# PCB_Reflow_Plate.net
KiCad netlist of a schematic drawn in Altium Designer
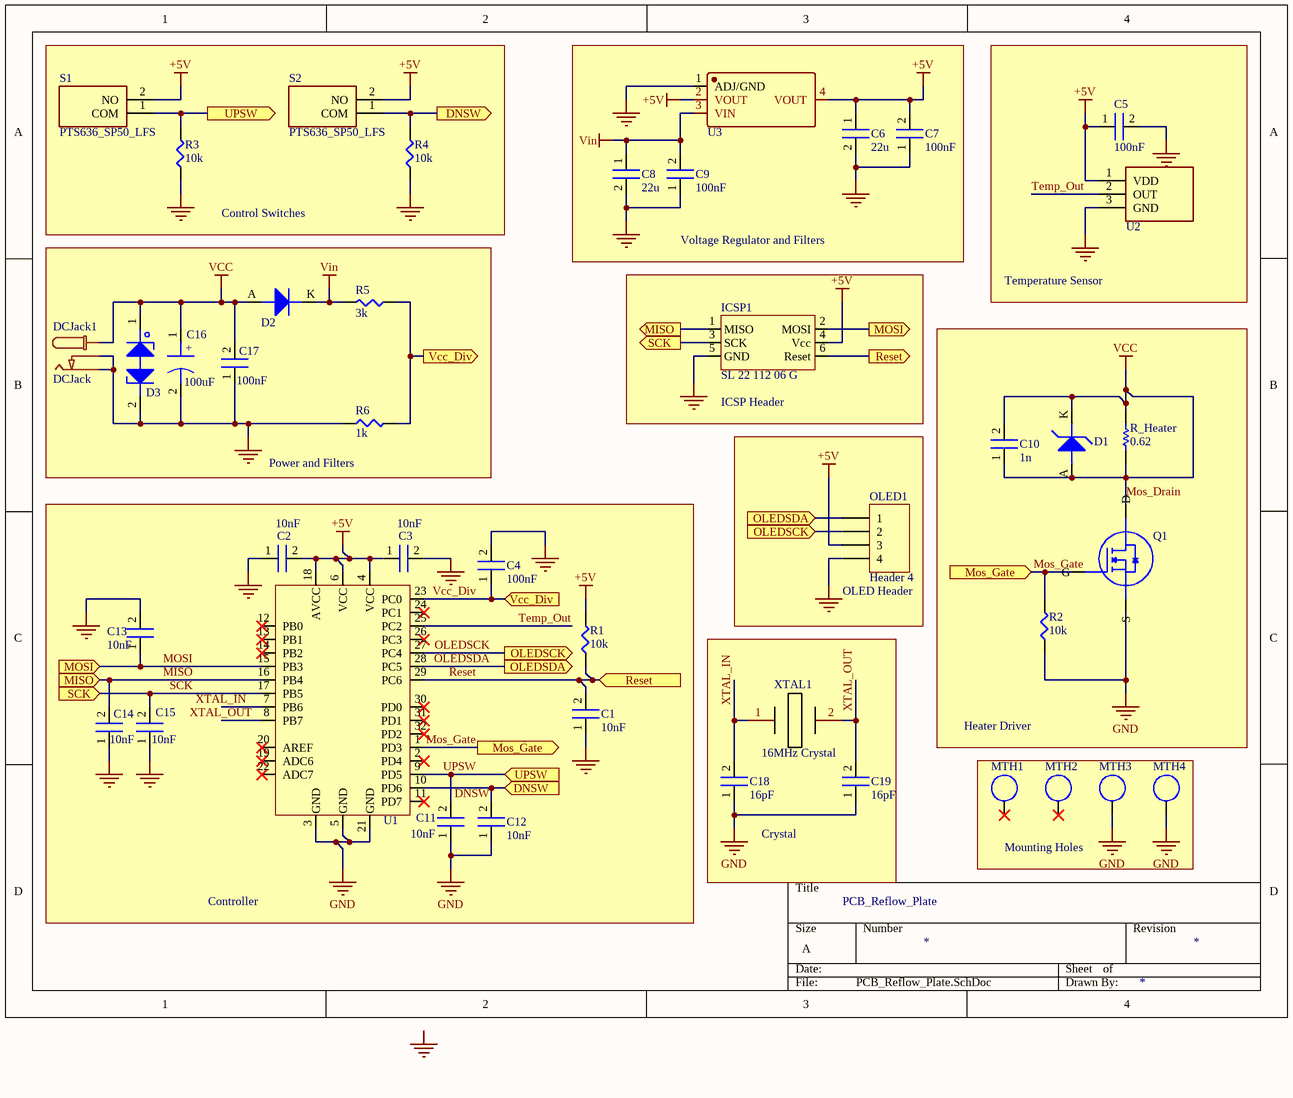
[diagram p0: PCB_Reflow_Plate.SchDoc]

(export (version "E")
  (design (tool "Eeschema 10.0.6"))
  (components
    (comp (ref "C1")
      (value "10n 0402")
      (footprint "0402B103J500CT")
      (description "Cap Ceramic 0.01uF 100V X7S 20% SMD 0402 125C Paper T/R")
      (fields
        (field (name "MANUFACTURER") "TDK")
        (field (name "MANUFACTURER PART NUMBER") "C1005X7S2A103M050BB")
        (field (name "CAPACITANCE") "10nF")
      )
      (libsource (lib "PCB_Reflow_Plate_SchLib") (part "C1005X7S2A103M050BB"))
    )
    (comp (ref "C2")
      (value "10n 0402")
      (footprint "0402B103J500CT")
      (description "Cap Ceramic 0.01uF 100V X7S 20% SMD 0402 125C Paper T/R")
      (fields
        (field (name "MANUFACTURER") "TDK")
        (field (name "MANUFACTURER PART NUMBER") "C1005X7S2A103M050BB")
        (field (name "CAPACITANCE") "10nF")
      )
      (libsource (lib "PCB_Reflow_Plate_SchLib") (part "C1005X7S2A103M050BB"))
    )
    (comp (ref "C3")
      (value "10n 0402")
      (footprint "0402B103J500CT")
      (description "Cap Ceramic 0.01uF 100V X7S 20% SMD 0402 125C Paper T/R")
      (fields
        (field (name "MANUFACTURER") "TDK")
        (field (name "MANUFACTURER PART NUMBER") "C1005X7S2A103M050BB")
        (field (name "CAPACITANCE") "10nF")
      )
      (libsource (lib "PCB_Reflow_Plate_SchLib") (part "C1005X7S2A103M050BB"))
    )
    (comp (ref "C4")
      (value "100n 0603")
      (footprint "0603B104K250CT")
      (description "CAP CER 0.1UF 100V X7R 0603")
      (fields
        (field (name "MANUFACTURER") "Murata")
        (field (name "MANUFACTURER PART NUMBER") "GRM188R72A104KA35D")
        (field (name "CAPACITANCE") "100nF")
      )
      (libsource (lib "PCB_Reflow_Plate_SchLib") (part "GRM188R72A104KA35D"))
    )
    (comp (ref "C5")
      (value "100n 0603")
      (footprint "0603B104K250CT")
      (description "CAP CER 0.1UF 100V X7R 0603")
      (fields
        (field (name "MANUFACTURER") "Murata")
        (field (name "MANUFACTURER PART NUMBER") "GRM188R72A104KA35D")
        (field (name "CAPACITANCE") "100nF")
      )
      (libsource (lib "PCB_Reflow_Plate_SchLib") (part "GRM188R72A104KA35D"))
    )
    (comp (ref "C6")
      (value "22u 0805")
      (footprint "CL21A226MAYNNNE")
      (description "25V 22uF X5R ±20% 0805 Multilayer Ceramic Capacitors MLCC - SMD/SMT ROHS")
      (fields
        (field (name "MANUFACTURER") "Samsung")
        (field (name "MANUFACTURER PART NUMBER") "CL21A226MAYNNNE")
        (field (name "CAPACITANCE") "22u")
      )
      (libsource (lib "PCB_Reflow_Plate_SchLib") (part "CL21A226MAYNNNE"))
    )
    (comp (ref "C7")
      (value "100n 0603")
      (footprint "0603B104K250CT")
      (description "CAP CER 0.1UF 100V X7R 0603")
      (fields
        (field (name "MANUFACTURER") "Murata")
        (field (name "MANUFACTURER PART NUMBER") "GRM188R72A104KA35D")
        (field (name "CAPACITANCE") "100nF")
      )
      (libsource (lib "PCB_Reflow_Plate_SchLib") (part "GRM188R72A104KA35D"))
    )
    (comp (ref "C8")
      (value "22u 0805")
      (footprint "CL21A226MAYNNNE")
      (description "25V 22uF X5R ±20% 0805 Multilayer Ceramic Capacitors MLCC - SMD/SMT ROHS")
      (fields
        (field (name "MANUFACTURER") "Samsung")
        (field (name "MANUFACTURER PART NUMBER") "CL21A226MAYNNNE")
        (field (name "CAPACITANCE") "22u")
      )
      (libsource (lib "PCB_Reflow_Plate_SchLib") (part "CL21A226MAYNNNE"))
    )
    (comp (ref "C9")
      (value "100n 0603")
      (footprint "0603B104K250CT")
      (description "CAP CER 0.1UF 100V X7R 0603")
      (fields
        (field (name "MANUFACTURER") "Murata")
        (field (name "MANUFACTURER PART NUMBER") "GRM188R72A104KA35D")
        (field (name "CAPACITANCE") "100nF")
      )
      (libsource (lib "PCB_Reflow_Plate_SchLib") (part "GRM188R72A104KA35D"))
    )
    (comp (ref "C10")
      (value "1n 0805")
      (footprint "FM21X102K501PXG")
      (description "0805 1 nF 250 V ±10% Tolerance X7R SMT Multilayer Ceramic Capacitor")
      (fields
        (field (name "MANUFACTURER") "Murata")
        (field (name "MANUFACTURER PART NUMBER") "GRM21AR72E102KW01D")
        (field (name "CAPACITANCE") "1n")
      )
      (libsource (lib "PCB_Reflow_Plate_SchLib") (part "GRM21AR72E102KW01D"))
    )
    (comp (ref "C11")
      (value "10n 0402")
      (footprint "0402B103J500CT")
      (description "Cap Ceramic 0.01uF 100V X7S 20% SMD 0402 125C Paper T/R")
      (fields
        (field (name "MANUFACTURER") "TDK")
        (field (name "MANUFACTURER PART NUMBER") "C1005X7S2A103M050BB")
        (field (name "CAPACITANCE") "10nF")
      )
      (libsource (lib "PCB_Reflow_Plate_SchLib") (part "C1005X7S2A103M050BB"))
    )
    (comp (ref "C12")
      (value "10n 0402")
      (footprint "0402B103J500CT")
      (description "Cap Ceramic 0.01uF 100V X7S 20% SMD 0402 125C Paper T/R")
      (fields
        (field (name "MANUFACTURER") "TDK")
        (field (name "MANUFACTURER PART NUMBER") "C1005X7S2A103M050BB")
        (field (name "CAPACITANCE") "10nF")
      )
      (libsource (lib "PCB_Reflow_Plate_SchLib") (part "C1005X7S2A103M050BB"))
    )
    (comp (ref "C13")
      (value "10n 0402")
      (footprint "0402B103J500CT")
      (description "Cap Ceramic 0.01uF 100V X7S 20% SMD 0402 125C Paper T/R")
      (fields
        (field (name "MANUFACTURER") "TDK")
        (field (name "MANUFACTURER PART NUMBER") "C1005X7S2A103M050BB")
        (field (name "CAPACITANCE") "10nF")
      )
      (libsource (lib "PCB_Reflow_Plate_SchLib") (part "C1005X7S2A103M050BB"))
    )
    (comp (ref "C14")
      (value "10n 0402")
      (footprint "0402B103J500CT")
      (description "Cap Ceramic 0.01uF 100V X7S 20% SMD 0402 125C Paper T/R")
      (fields
        (field (name "MANUFACTURER") "TDK")
        (field (name "MANUFACTURER PART NUMBER") "C1005X7S2A103M050BB")
        (field (name "CAPACITANCE") "10nF")
      )
      (libsource (lib "PCB_Reflow_Plate_SchLib") (part "C1005X7S2A103M050BB"))
    )
    (comp (ref "C15")
      (value "10n 0402")
      (footprint "0402B103J500CT")
      (description "Cap Ceramic 0.01uF 100V X7S 20% SMD 0402 125C Paper T/R")
      (fields
        (field (name "MANUFACTURER") "TDK")
        (field (name "MANUFACTURER PART NUMBER") "C1005X7S2A103M050BB")
        (field (name "CAPACITANCE") "10nF")
      )
      (libsource (lib "PCB_Reflow_Plate_SchLib") (part "C1005X7S2A103M050BB"))
    )
    (comp (ref "C16")
      (value "100u SMD Polarized")
      (footprint "UWT1V101MCL1GS")
      (fields
        (field (name "MANUFACTURER") "Nichicon")
        (field (name "MANUFACTURER PART NUMBER") "UWT1V101MCL1GS")
        (field (name "TOLERANCE") "20%")
        (field (name "CAPACITANCE") "100uF")
      )
      (libsource (lib "PCB_Reflow_Plate_SchLib") (part "UWT1V101MCL1GS"))
    )
    (comp (ref "C17")
      (value "100n 0603")
      (footprint "0603B104K250CT")
      (description "CAP CER 0.1UF 100V X7R 0603")
      (fields
        (field (name "MANUFACTURER") "Murata")
        (field (name "MANUFACTURER PART NUMBER") "GRM188R72A104KA35D")
        (field (name "CAPACITANCE") "100nF")
      )
      (libsource (lib "PCB_Reflow_Plate_SchLib") (part "GRM188R72A104KA35D"))
    )
    (comp (ref "C18")
      (value "16pf 0603 Capacitor")
      (footprint "NMC0603NPO160J50TRPF")
      (description "Cap Ceramic 16pF 50V C0G 5% SMD 0603 125°C Paper T/R")
      (fields
        (field (name "MANUFACTURER") "NIC Components")
        (field (name "MANUFACTURER PART NUMBER") "NMC0603NPO160J50TRPF")
        (field (name "CAPACITANCE") "16pF")
      )
      (libsource (lib "PCB_Reflow_Plate_SchLib") (part "NMC0603NPO160J50TRPF"))
    )
    (comp (ref "C19")
      (value "16pf 0603 Capacitor")
      (footprint "NMC0603NPO160J50TRPF")
      (description "Cap Ceramic 16pF 50V C0G 5% SMD 0603 125°C Paper T/R")
      (fields
        (field (name "MANUFACTURER") "NIC Components")
        (field (name "MANUFACTURER PART NUMBER") "NMC0603NPO160J50TRPF")
        (field (name "CAPACITANCE") "16pF")
      )
      (libsource (lib "PCB_Reflow_Plate_SchLib") (part "NMC0603NPO160J50TRPF"))
    )
    (comp (ref "D1")
      (value "Zener Diode")
      (footprint "MMSZ24T1G")
      (description "Zener Single Diode, 24 V, 500 mW, SOD-123, 5 %, 2, 150 C RoHS Compliant: Yes")
      (fields
        (field (name "MANUFACTURER") "ON Semiconductor")
        (field (name "MANUFACTURER PART NUMBER") "MMSZ24T1G")
      )
      (libsource (lib "PCB_Reflow_Plate_SchLib") (part "MMSZ24T1G"))
    )
    (comp (ref "D2")
      (value "Diode")
      (footprint "1N4448X-TP")
      (description "1N4448X Series 4 A 75 V 150 mW Surface Mount Switching Diode - SOD-523")
      (fields (field (name "MANUFACTURER") "MCC") (field (name "MANUFACTURER PART NUMBER") "1N4448X-TP"))
      (libsource (lib "PCB_Reflow_Plate_SchLib") (part "1N4448X-TP"))
    )
    (comp (ref "D3")
      (value "TVS bi-directional")
      (footprint "PESD18VF1BLYL")
      (description "TVS DIODE 18VWM 17VC SOD882")
      (fields
        (field (name "MANUFACTURER") "Nexperia")
        (field (name "MANUFACTURER PART NUMBER") "PESD18VF1BLYL")
      )
      (libsource (lib "PCB_Reflow_Plate_SchLib") (part "PESD18VF1BLYL"))
    )
    (comp (ref "DCJack1")
      (value "DCJack")
      (footprint "KLDX-0202-B")
      (description "Conn Power PIN 2 POS Solder RA Thru-Hole 3 Terminal 1 Port")
      (fields (field (name "MANUFACTURER") "Kycon") (field (name "MANUFACTURER PART NUMBER") "KLDX-0202-B"))
      (libsource (lib "PCB_Reflow_Plate_SchLib") (part "KLDX-0202-B"))
    )
    (comp (ref "ICSP1")
      (value "SL 22 112 06 G")
      (footprint "SL 22 112 06 G")
      (description "Conn Unshrouded Header M 6 POS 2.54mm Solder ST Thru-Hole")
      (fields (field (name "MANUFACTURER") "Fischer Elektronik"))
      (libsource (lib "PCB_Reflow_Plate_SchLib") (part "SL 22 112 06 G"))
    )
    (comp (ref "MTH1")
      (value "Mounting Hole 6mm outer 3mm inner")
      (footprint "MTH_6mmOD_3mmID")
      (description "Mounting Hole 6mm outer 3mm inner drill")
      (libsource (lib "PCB_Reflow_Plate_SchLib") (part "MTH_6mmOD_3mmID"))
    )
    (comp (ref "MTH2")
      (value "Mounting Hole 6mm outer 3mm inner")
      (footprint "MTH_6mmOD_3mmID")
      (description "Mounting Hole 6mm outer 3mm inner drill")
      (libsource (lib "PCB_Reflow_Plate_SchLib") (part "MTH_6mmOD_3mmID"))
    )
    (comp (ref "MTH3")
      (value "Mounting Hole 6mm outer 3mm inner")
      (footprint "MTH_6mmOD_3mmID")
      (description "Mounting Hole 6mm outer 3mm inner drill")
      (libsource (lib "PCB_Reflow_Plate_SchLib") (part "MTH_6mmOD_3mmID"))
    )
    (comp (ref "MTH4")
      (value "Mounting Hole 6mm outer 3mm inner")
      (footprint "MTH_6mmOD_3mmID")
      (description "Mounting Hole 6mm outer 3mm inner drill")
      (libsource (lib "PCB_Reflow_Plate_SchLib") (part "MTH_6mmOD_3mmID"))
    )
    (comp (ref "OLED1")
      (value "Header 4")
      (footprint "HDR1X4")
      (description "Header, 4-Pin")
      (fields (field (name "PUBLISHER") "Altium Limited"))
      (libsource (lib "Miscellaneous Connectors") (part "Header 4"))
    )
    (comp (ref "Q1")
      (value "Mosfet DPAK")
      (footprint "AOD442")
      (description "Trans MOSFET N-CH 60V 37A 3-Pin(2+Tab) DPAK")
      (fields
        (field (name "MANUFACTURER") "Alpha & Omega Semiconductor")
        (field (name "MANUFACTURER PART NUMBER") "AOD442")
      )
      (libsource (lib "PCB_Reflow_Plate_SchLib") (part "AOD442"))
    )
    (comp (ref "R1")
      (value "10k 0603")
      (footprint "RTT03103JTP")
      (description "Res Thin Film 0603 10K Ohm 0.5% 0.1W(1/10W) ±50ppm/°C Pad SMD T/R")
      (fields
        (field (name "MANUFACTURER") "Yageo")
        (field (name "MANUFACTURER PART NUMBER") "RT0603DRE0710KL")
        (field (name "RESISTANCE") "10k")
      )
      (libsource (lib "PCB_Reflow_Plate_SchLib") (part "RT0603DRE0710KL"))
    )
    (comp (ref "R2")
      (value "10k 0603")
      (footprint "RTT03103JTP")
      (description "Res Thin Film 0603 10K Ohm 0.5% 0.1W(1/10W) ±50ppm/°C Pad SMD T/R")
      (fields
        (field (name "MANUFACTURER") "Yageo")
        (field (name "MANUFACTURER PART NUMBER") "RT0603DRE0710KL")
        (field (name "RESISTANCE") "10k")
      )
      (libsource (lib "PCB_Reflow_Plate_SchLib") (part "RT0603DRE0710KL"))
    )
    (comp (ref "R3")
      (value "10k 0603")
      (footprint "RTT03103JTP")
      (description "Res Thin Film 0603 10K Ohm 0.5% 0.1W(1/10W) ±50ppm/°C Pad SMD T/R")
      (fields
        (field (name "MANUFACTURER") "Yageo")
        (field (name "MANUFACTURER PART NUMBER") "RT0603DRE0710KL")
        (field (name "RESISTANCE") "10k")
      )
      (libsource (lib "PCB_Reflow_Plate_SchLib") (part "RT0603DRE0710KL"))
    )
    (comp (ref "R4")
      (value "10k 0603")
      (footprint "RTT03103JTP")
      (description "Res Thin Film 0603 10K Ohm 0.5% 0.1W(1/10W) ±50ppm/°C Pad SMD T/R")
      (fields
        (field (name "MANUFACTURER") "Yageo")
        (field (name "MANUFACTURER PART NUMBER") "RT0603DRE0710KL")
        (field (name "RESISTANCE") "10k")
      )
      (libsource (lib "PCB_Reflow_Plate_SchLib") (part "RT0603DRE0710KL"))
    )
    (comp (ref "R5")
      (value "3k 0805")
      (footprint "RTT05302JTP")
      (description "Res Thick Film 0805 3K Ohm 1% 0.125W(1/8W) ±100ppm/C Pad SMD T/R")
      (fields
        (field (name "MANUFACTURER") "Yageo")
        (field (name "MANUFACTURER PART NUMBER") "RC0805FR-073KL")
        (field (name "RESISTANCE") "3k")
      )
      (libsource (lib "PCB_Reflow_Plate_SchLib") (part "RC0805FR-073KL"))
    )
    (comp (ref "R6")
      (value "1k 0805")
      (footprint "CR0805-FX-1001ELF")
      (description "125mW ±100ppm/℃ ±1% 1kΩ 0805 Chip Resistor - Surface Mount ROHS")
      (fields
        (field (name "MANUFACTURER") "Bourns")
        (field (name "MANUFACTURER PART NUMBER") "CR0805-FX-1001ELF")
        (field (name "RESISTANCE") "1k")
      )
      (libsource (lib "PCB_Reflow_Plate_SchLib") (part "CR0805-FX-1001ELF"))
    )
    (comp (ref "R_Heater")
      (value "0.62")
      (description "Resistor")
      (libsource (lib "Simulation Generic Components") (part "Resistor"))
    )
    (comp (ref "S1")
      (value "PTS636_SP50_LFS")
      (footprint "PTS636_SP50_LFS")
      (description "Switch")
      (fields
        (field (name "MANUFACTURER") "C & K COMPONENTS")
        (field (name "MANUFACTURER PART NUMBER") "PTS636 SP50 LFS")
      )
      (libsource (lib "PCB_Reflow_Plate_SchLib") (part "PTS636_SP50_LFS"))
    )
    (comp (ref "S2")
      (value "PTS636_SP50_LFS")
      (footprint "PTS636_SP50_LFS")
      (description "Switch")
      (fields
        (field (name "MANUFACTURER") "C & K COMPONENTS")
        (field (name "MANUFACTURER PART NUMBER") "PTS636 SP50 LFS")
      )
      (libsource (lib "PCB_Reflow_Plate_SchLib") (part "PTS636_SP50_LFS"))
    )
    (comp (ref "U1")
      (value "ATMEGA328P-AU")
      (footprint "atmega328p-au")
      (fields (field (name "MANUFACTURER") "Microchip"))
      (libsource (lib "PCB_Reflow_Plate_SchLib") (part "ATMEGA328P-AU"))
    )
    (comp (ref "U2")
      (value "LMT85LP")
      (footprint "LMT85LP")
      (description "1.8V-Capable, 10 uA Analog Output Temperature Sensor in SC70 and TO-92 3-TO-92 -50 to 150")
      (fields (field (name "MANUFACTURER") "Texas Instruments"))
      (libsource (lib "PCB_Reflow_Plate_SchLib") (part "LMT85LP"))
    )
    (comp (ref "U3")
      (value "AMS1117-5.0")
      (footprint "AMS1117-5.0")
      (fields (field (name "MANUFACTURER") "WPMtek"))
      (libsource (lib "PCB_Reflow_Plate_SchLib") (part "AMS1117-5.0"))
    )
    (comp (ref "XTAL1")
      (value "16MHz Crystal")
      (footprint "ABM7-16.000MHZ-D2Y-T")
      (description "Crystal 16MHz ±20ppm (Tol) ±30ppm (Stability) 18pF FUND 50Ohm 2-Pin Mini-CSMD T/R")
      (fields
        (field (name "MANUFACTURER") "Abracon")
        (field (name "MANUFACTURER PART NUMBER") "ABM7-16.000MHZ-D2Y-T")
      )
      (libsource (lib "PCB_Reflow_Plate_SchLib") (part "ABM7-16.000MHZ-D2Y-T"))
    )
  )
  (nets
    (net (code "1") (name "+5V") (class "Default")
      (node (ref "C2") (pin "2") (pinfunction "2_2") (pintype "passive"))
      (node (ref "C3") (pin "1") (pinfunction "1_1") (pintype "passive"))
      (node (ref "C5") (pin "1") (pinfunction "1_1") (pintype "passive"))
      (node (ref "C6") (pin "1") (pinfunction "1_1") (pintype "passive"))
      (node (ref "C7") (pin "2") (pinfunction "2_2") (pintype "passive"))
      (node (ref "ICSP1") (pin "4") (pinfunction "Vcc_4") (pintype "passive"))
      (node (ref "OLED1") (pin "3") (pinfunction "3_3") (pintype "passive"))
      (node (ref "R1") (pin "2") (pinfunction "2_2") (pintype "passive"))
      (node (ref "S1") (pin "2") (pinfunction "NO_2") (pintype "passive"))
      (node (ref "S2") (pin "2") (pinfunction "NO_2") (pintype "passive"))
      (node (ref "U1") (pin "18") (pinfunction "AVCC_18") (pintype "passive"))
      (node (ref "U1") (pin "4") (pinfunction "VCC_4") (pintype "passive"))
      (node (ref "U1") (pin "6") (pinfunction "VCC_6") (pintype "passive"))
      (node (ref "U2") (pin "1") (pinfunction "VDD_1") (pintype "passive"))
      (node (ref "U3") (pin "2") (pinfunction "VOUT_2") (pintype "passive"))
      (node (ref "U3") (pin "4") (pinfunction "VOUT_4") (pintype "passive"))
    )
    (net (code "2") (name "/DNSW") (class "Default")
      (node (ref "C12") (pin "2") (pinfunction "2_2") (pintype "passive"))
      (node (ref "R4") (pin "2") (pinfunction "2_2") (pintype "passive"))
      (node (ref "S2") (pin "1") (pinfunction "COM_1") (pintype "passive"))
      (node (ref "U1") (pin "10") (pinfunction "PD6_10") (pintype "passive"))
    )
    (net (code "3") (name "/MISO") (class "Default")
      (node (ref "C14") (pin "2") (pinfunction "2_2") (pintype "passive"))
      (node (ref "ICSP1") (pin "1") (pinfunction "MISO_1") (pintype "passive"))
      (node (ref "U1") (pin "16") (pinfunction "PB4_16") (pintype "passive"))
    )
    (net (code "4") (name "/MOSI") (class "Default")
      (node (ref "C13") (pin "1") (pinfunction "1_1") (pintype "passive"))
      (node (ref "ICSP1") (pin "2") (pinfunction "MOSI_2") (pintype "passive"))
      (node (ref "U1") (pin "15") (pinfunction "PB3_15") (pintype "passive"))
    )
    (net (code "5") (name "/Mos_Gate") (class "Default")
      (node (ref "Q1") (pin "3") (pinfunction "G_3") (pintype "passive"))
      (node (ref "R2") (pin "2") (pinfunction "2_2") (pintype "passive"))
      (node (ref "U1") (pin "1") (pinfunction "PD3_1") (pintype "passive"))
    )
    (net (code "6") (name "/OLEDSCK") (class "Default")
      (node (ref "OLED1") (pin "2") (pinfunction "2_2") (pintype "passive"))
      (node (ref "U1") (pin "27") (pinfunction "PC4_27") (pintype "passive"))
    )
    (net (code "7") (name "/OLEDSDA") (class "Default")
      (node (ref "OLED1") (pin "1") (pinfunction "1_1") (pintype "passive"))
      (node (ref "U1") (pin "28") (pinfunction "PC5_28") (pintype "passive"))
    )
    (net (code "8") (name "/Reset") (class "Default")
      (node (ref "C1") (pin "2") (pinfunction "2_2") (pintype "passive"))
      (node (ref "ICSP1") (pin "6") (pinfunction "Reset_6") (pintype "passive"))
      (node (ref "R1") (pin "1") (pinfunction "1_1") (pintype "passive"))
      (node (ref "U1") (pin "29") (pinfunction "PC6_29") (pintype "passive"))
    )
    (net (code "9") (name "/SCK") (class "Default")
      (node (ref "C15") (pin "2") (pinfunction "2_2") (pintype "passive"))
      (node (ref "ICSP1") (pin "3") (pinfunction "SCK_3") (pintype "passive"))
      (node (ref "U1") (pin "17") (pinfunction "PB5_17") (pintype "passive"))
    )
    (net (code "10") (name "/Temp_Out") (class "Default")
      (node (ref "U1") (pin "25") (pinfunction "PC2_25") (pintype "passive"))
      (node (ref "U2") (pin "2") (pinfunction "OUT_2") (pintype "passive"))
    )
    (net (code "11") (name "/UPSW") (class "Default")
      (node (ref "C11") (pin "2") (pinfunction "2_2") (pintype "passive"))
      (node (ref "R3") (pin "2") (pinfunction "2_2") (pintype "passive"))
      (node (ref "S1") (pin "1") (pinfunction "COM_1") (pintype "passive"))
      (node (ref "U1") (pin "9") (pinfunction "PD5_9") (pintype "passive"))
    )
    (net (code "12") (name "/Vcc_Div") (class "Default")
      (node (ref "C4") (pin "1") (pinfunction "1_1") (pintype "passive"))
      (node (ref "R5") (pin "1") (pinfunction "1_1") (pintype "passive"))
      (node (ref "R6") (pin "2") (pinfunction "2_2") (pintype "passive"))
      (node (ref "U1") (pin "23") (pinfunction "PC0_23") (pintype "passive"))
    )
    (net (code "13") (name "/XTAL_IN") (class "Default")
      (node (ref "C18") (pin "2") (pinfunction "2_2") (pintype "passive"))
      (node (ref "U1") (pin "7") (pinfunction "PB6_7") (pintype "passive"))
      (node (ref "XTAL1") (pin "1") (pinfunction "1_1") (pintype "passive"))
    )
    (net (code "14") (name "/XTAL_OUT") (class "Default")
      (node (ref "C19") (pin "2") (pinfunction "2_2") (pintype "passive"))
      (node (ref "U1") (pin "8") (pinfunction "PB7_8") (pintype "passive"))
      (node (ref "XTAL1") (pin "2") (pinfunction "2_2") (pintype "passive"))
    )
    (net (code "15") (name "GND") (class "Default")
      (node (ref "C1") (pin "1") (pinfunction "1_1") (pintype "passive"))
      (node (ref "C11") (pin "1") (pinfunction "1_1") (pintype "passive"))
      (node (ref "C12") (pin "1") (pinfunction "1_1") (pintype "passive"))
      (node (ref "C13") (pin "2") (pinfunction "2_2") (pintype "passive"))
      (node (ref "C14") (pin "1") (pinfunction "1_1") (pintype "passive"))
      (node (ref "C15") (pin "1") (pinfunction "1_1") (pintype "passive"))
      (node (ref "C16") (pin "2") (pinfunction "2_2") (pintype "passive"))
      (node (ref "C17") (pin "1") (pinfunction "1_1") (pintype "passive"))
      (node (ref "C18") (pin "1") (pinfunction "1_1") (pintype "passive"))
      (node (ref "C19") (pin "1") (pinfunction "1_1") (pintype "passive"))
      (node (ref "C2") (pin "1") (pinfunction "1_1") (pintype "passive"))
      (node (ref "C3") (pin "2") (pinfunction "2_2") (pintype "passive"))
      (node (ref "C4") (pin "2") (pinfunction "2_2") (pintype "passive"))
      (node (ref "C5") (pin "2") (pinfunction "2_2") (pintype "passive"))
      (node (ref "C6") (pin "2") (pinfunction "2_2") (pintype "passive"))
      (node (ref "C7") (pin "1") (pinfunction "1_1") (pintype "passive"))
      (node (ref "C8") (pin "2") (pinfunction "2_2") (pintype "passive"))
      (node (ref "C9") (pin "1") (pinfunction "1_1") (pintype "passive"))
      (node (ref "D3") (pin "2") (pinfunction "2_2") (pintype "passive"))
      (node (ref "DCJack1") (pin "P2") (pinfunction "P2_P2") (pintype "passive"))
      (node (ref "DCJack1") (pin "P3") (pinfunction "P3_P3") (pintype "passive"))
      (node (ref "ICSP1") (pin "5") (pinfunction "GND_5") (pintype "passive"))
      (node (ref "MTH3") (pin "1") (pinfunction "1_1") (pintype "passive"))
      (node (ref "MTH4") (pin "1") (pinfunction "1_1") (pintype "passive"))
      (node (ref "OLED1") (pin "4") (pinfunction "4_4") (pintype "passive"))
      (node (ref "Q1") (pin "2") (pinfunction "S_2") (pintype "passive"))
      (node (ref "R2") (pin "1") (pinfunction "1_1") (pintype "passive"))
      (node (ref "R3") (pin "1") (pinfunction "1_1") (pintype "passive"))
      (node (ref "R4") (pin "1") (pinfunction "1_1") (pintype "passive"))
      (node (ref "R6") (pin "1") (pinfunction "1_1") (pintype "passive"))
      (node (ref "U1") (pin "21") (pinfunction "GND_21") (pintype "passive"))
      (node (ref "U1") (pin "3") (pinfunction "GND_3") (pintype "passive"))
      (node (ref "U1") (pin "5") (pinfunction "GND_5") (pintype "passive"))
      (node (ref "U2") (pin "3") (pinfunction "GND_3") (pintype "passive"))
      (node (ref "U3") (pin "1") (pinfunction "ADJ/GND_1") (pintype "passive"))
    )
    (net (code "16") (name "VCC") (class "Default")
      (node (ref "C10") (pin "1") (pinfunction "1_1") (pintype "passive"))
      (node (ref "C10") (pin "2") (pinfunction "2_2") (pintype "passive"))
      (node (ref "C16") (pin "1") (pinfunction "1_1") (pintype "passive"))
      (node (ref "C17") (pin "2") (pinfunction "2_2") (pintype "passive"))
      (node (ref "D1") (pin "A") (pinfunction "A_A") (pintype "passive"))
      (node (ref "D1") (pin "K") (pinfunction "K_K") (pintype "passive"))
      (node (ref "D2") (pin "A") (pinfunction "1_A") (pintype "passive"))
      (node (ref "D3") (pin "1") (pinfunction "1_1") (pintype "passive"))
      (node (ref "DCJack1") (pin "P1") (pinfunction "P1_P1") (pintype "passive"))
      (node (ref "Q1") (pin "1") (pinfunction "D_1") (pintype "passive"))
      (node (ref "R_Heater") (pin "1") (pinfunction "1_1") (pintype "passive"))
      (node (ref "R_Heater") (pin "2") (pinfunction "2_2") (pintype "passive"))
    )
    (net (code "17") (name "Vin") (class "Default")
      (node (ref "C8") (pin "1") (pinfunction "1_1") (pintype "passive"))
      (node (ref "C9") (pin "2") (pinfunction "2_2") (pintype "passive"))
      (node (ref "D2") (pin "K") (pinfunction "2_K") (pintype "passive"))
      (node (ref "R5") (pin "2") (pinfunction "2_2") (pintype "passive"))
      (node (ref "U3") (pin "3") (pinfunction "VIN_3") (pintype "passive"))
    )
    (net (code "18") (name "unconnected-(MTH1-Pad1)") (class "Default")
      (node (ref "MTH1") (pin "1") (pinfunction "1_1") (pintype "passive+no_connect"))
    )
    (net (code "19") (name "unconnected-(MTH2-Pad1)") (class "Default")
      (node (ref "MTH2") (pin "1") (pinfunction "1_1") (pintype "passive+no_connect"))
    )
    (net (code "20") (name "unconnected-(U1-ADC6-Pad19)") (class "Default")
      (node (ref "U1") (pin "19") (pinfunction "ADC6_19") (pintype "passive+no_connect"))
    )
    (net (code "21") (name "unconnected-(U1-ADC7-Pad22)") (class "Default")
      (node (ref "U1") (pin "22") (pinfunction "ADC7_22") (pintype "passive+no_connect"))
    )
    (net (code "22") (name "unconnected-(U1-AREF-Pad20)") (class "Default")
      (node (ref "U1") (pin "20") (pinfunction "AREF_20") (pintype "passive+no_connect"))
    )
    (net (code "23") (name "unconnected-(U1-PB0-Pad12)") (class "Default")
      (node (ref "U1") (pin "12") (pinfunction "PB0_12") (pintype "passive+no_connect"))
    )
    (net (code "24") (name "unconnected-(U1-PB1-Pad13)") (class "Default")
      (node (ref "U1") (pin "13") (pinfunction "PB1_13") (pintype "passive+no_connect"))
    )
    (net (code "25") (name "unconnected-(U1-PB2-Pad14)") (class "Default")
      (node (ref "U1") (pin "14") (pinfunction "PB2_14") (pintype "passive+no_connect"))
    )
    (net (code "26") (name "unconnected-(U1-PC1-Pad24)") (class "Default")
      (node (ref "U1") (pin "24") (pinfunction "PC1_24") (pintype "passive+no_connect"))
    )
    (net (code "27") (name "unconnected-(U1-PC3-Pad26)") (class "Default")
      (node (ref "U1") (pin "26") (pinfunction "PC3_26") (pintype "passive+no_connect"))
    )
    (net (code "28") (name "unconnected-(U1-PD0-Pad30)") (class "Default")
      (node (ref "U1") (pin "30") (pinfunction "PD0_30") (pintype "passive+no_connect"))
    )
    (net (code "29") (name "unconnected-(U1-PD1-Pad31)") (class "Default")
      (node (ref "U1") (pin "31") (pinfunction "PD1_31") (pintype "passive+no_connect"))
    )
    (net (code "30") (name "unconnected-(U1-PD2-Pad32)") (class "Default")
      (node (ref "U1") (pin "32") (pinfunction "PD2_32") (pintype "passive+no_connect"))
    )
    (net (code "31") (name "unconnected-(U1-PD4-Pad2)") (class "Default")
      (node (ref "U1") (pin "2") (pinfunction "PD4_2") (pintype "passive+no_connect"))
    )
    (net (code "32") (name "unconnected-(U1-PD7-Pad11)") (class "Default")
      (node (ref "U1") (pin "11") (pinfunction "PD7_11") (pintype "passive+no_connect"))
    )
  )
)
